# pca9306-breakout.net
KiCad netlist of a schematic drawn in EAGLE
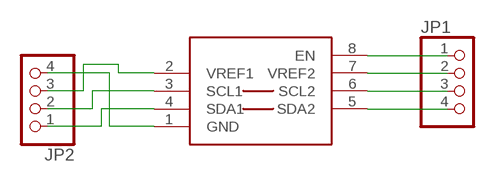
[diagram p0: schematic, sheet 1]

(export (version "E")
  (design (tool "Eeschema 10.0.6"))
  (components
    (comp (ref "JP1")
      (value "PINHD-1X4")
      (footprint "eagle-import:1X04")
      (libsource (lib "eagle-import") (part "PINHD-1X4"))
    )
    (comp (ref "JP2")
      (value "PINHD-1X4")
      (footprint "eagle-import:1X04")
      (libsource (lib "eagle-import") (part "PINHD-1X4"))
    )
    (comp (ref "U11")
      (value "PCA9306")
      (footprint "eagle-import:PSOP-8")
      (libsource (lib "eagle-import") (part "PCA9306"))
    )
  )
  (nets
    (net (code "1") (name "Net-(U11-EN)") (class "Default")
      (node (ref "JP1") (pin "1") (pinfunction "1_1") (pintype "passive"))
      (node (ref "U11") (pin "8") (pinfunction "EN_8") (pintype "bidirectional"))
    )
    (net (code "2") (name "Net-(U11-GND)") (class "Default")
      (node (ref "JP2") (pin "4") (pinfunction "4_4") (pintype "passive"))
      (node (ref "U11") (pin "1") (pinfunction "GND_1") (pintype "bidirectional"))
    )
    (net (code "3") (name "Net-(U11-SCL1)") (class "Default")
      (node (ref "JP2") (pin "2") (pinfunction "2_2") (pintype "passive"))
      (node (ref "U11") (pin "3") (pinfunction "SCL1_3") (pintype "bidirectional"))
    )
    (net (code "4") (name "Net-(U11-SCL2)") (class "Default")
      (node (ref "JP1") (pin "3") (pinfunction "3_3") (pintype "passive"))
      (node (ref "U11") (pin "6") (pinfunction "SCL2_6") (pintype "bidirectional"))
    )
    (net (code "5") (name "Net-(U11-SDA1)") (class "Default")
      (node (ref "JP2") (pin "1") (pinfunction "1_1") (pintype "passive"))
      (node (ref "U11") (pin "4") (pinfunction "SDA1_4") (pintype "bidirectional"))
    )
    (net (code "6") (name "Net-(U11-SDA2)") (class "Default")
      (node (ref "JP1") (pin "4") (pinfunction "4_4") (pintype "passive"))
      (node (ref "U11") (pin "5") (pinfunction "SDA2_5") (pintype "bidirectional"))
    )
    (net (code "7") (name "Net-(U11-VREF1)") (class "Default")
      (node (ref "JP2") (pin "3") (pinfunction "3_3") (pintype "passive"))
      (node (ref "U11") (pin "2") (pinfunction "VREF1_2") (pintype "bidirectional"))
    )
    (net (code "8") (name "Net-(U11-VREF2)") (class "Default")
      (node (ref "JP1") (pin "2") (pinfunction "2_2") (pintype "passive"))
      (node (ref "U11") (pin "7") (pinfunction "VREF2_7") (pintype "bidirectional"))
    )
  )
)
